# Current-LoadSwitches_1V8.net
KiCad netlist of a schematic drawn in Altium Designer
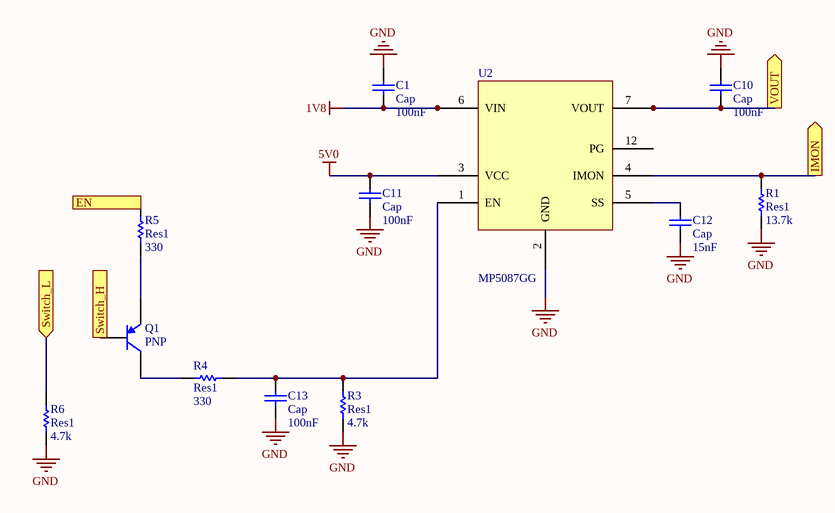
[diagram p0: Current-LoadSwitches 1V8.SchDoc]

(export (version "E")
  (design (tool "Eeschema 10.0.6"))
  (components
    (comp (ref "C1")
      (value "Cap")
      (footprint "0402-A")
      (description "Capacitor")
      (fields (field (name "ALTIUM_VALUE") "100nF") (field (name "PUBLISHER") "Altium Limited"))
      (libsource (lib "Miscellaneous Devices") (part "Cap"))
    )
    (comp (ref "C10")
      (value "Cap")
      (footprint "0402-A")
      (description "Capacitor")
      (fields (field (name "ALTIUM_VALUE") "100nF") (field (name "PUBLISHER") "Altium Limited"))
      (libsource (lib "Miscellaneous Devices") (part "Cap"))
    )
    (comp (ref "C11")
      (value "Cap")
      (footprint "0402-A")
      (description "Capacitor")
      (fields (field (name "ALTIUM_VALUE") "100nF") (field (name "PUBLISHER") "Altium Limited"))
      (libsource (lib "Miscellaneous Devices") (part "Cap"))
    )
    (comp (ref "C12")
      (value "Cap")
      (footprint "0402-A")
      (description "Capacitor")
      (fields (field (name "ALTIUM_VALUE") "15nF") (field (name "PUBLISHER") "Altium Limited"))
      (libsource (lib "Miscellaneous Devices") (part "Cap"))
    )
    (comp (ref "C13")
      (value "Cap")
      (footprint "0402-A")
      (description "Capacitor")
      (fields (field (name "ALTIUM_VALUE") "100nF") (field (name "PUBLISHER") "Altium Limited"))
      (libsource (lib "Miscellaneous Devices") (part "Cap"))
    )
    (comp (ref "Q1")
      (value "PNP")
      (footprint "SOT-23B_N")
      (description "PNP Bipolar Transistor")
      (fields (field (name "PUBLISHER") "Altium Limited"))
      (libsource (lib "Miscellaneous Devices") (part "PNP"))
    )
    (comp (ref "R1")
      (value "Res1")
      (footprint "0402-A")
      (description "Resistor")
      (fields (field (name "ALTIUM_VALUE") "13.7k") (field (name "PUBLISHER") "Altium Limited"))
      (libsource (lib "Miscellaneous Devices") (part "Res1"))
    )
    (comp (ref "R3")
      (value "Res1")
      (footprint "0402-A")
      (description "Resistor")
      (fields (field (name "ALTIUM_VALUE") "4.7k") (field (name "PUBLISHER") "Altium Limited"))
      (libsource (lib "Miscellaneous Devices") (part "Res1"))
    )
    (comp (ref "R4")
      (value "Res1")
      (footprint "0402-A")
      (description "Resistor")
      (fields (field (name "ALTIUM_VALUE") "330") (field (name "PUBLISHER") "Altium Limited"))
      (libsource (lib "Miscellaneous Devices") (part "Res1"))
    )
    (comp (ref "R5")
      (value "Res1")
      (footprint "0402-A")
      (description "Resistor")
      (fields (field (name "ALTIUM_VALUE") "330") (field (name "PUBLISHER") "Altium Limited"))
      (libsource (lib "Miscellaneous Devices") (part "Res1"))
    )
    (comp (ref "R6")
      (value "Res1")
      (footprint "0402-A")
      (description "Resistor")
      (fields (field (name "ALTIUM_VALUE") "4.7k") (field (name "PUBLISHER") "Altium Limited"))
      (libsource (lib "Miscellaneous Devices") (part "Res1"))
    )
    (comp (ref "U2")
      (value "MP5087GG")
      (footprint "MP5087GG-Z")
      (libsource (lib "MP5087GG-Z") (part "Component_1"))
    )
  )
  (nets
    (net (code "1") (name "/EN") (class "Default")
      (node (ref "R5") (pin "2") (pinfunction "2_2") (pintype "passive"))
    )
    (net (code "2") (name "/IMON") (class "Default")
      (node (ref "R1") (pin "2") (pinfunction "2_2") (pintype "passive"))
      (node (ref "U2") (pin "4") (pinfunction "IMON_4") (pintype "passive"))
    )
    (net (code "3") (name "/Switch_H") (class "Default")
      (node (ref "Q1") (pin "2") (pinfunction "B_2") (pintype "passive"))
    )
    (net (code "4") (name "/Switch_L") (class "Default")
      (node (ref "R6") (pin "2") (pinfunction "2_2") (pintype "passive"))
    )
    (net (code "5") (name "/VOUT") (class "Default")
      (node (ref "C10") (pin "1") (pinfunction "1_1") (pintype "passive"))
      (node (ref "U2") (pin "10") (pinfunction "VOUT_10") (pintype "passive"))
      (node (ref "U2") (pin "7") (pinfunction "VOUT_7") (pintype "passive"))
      (node (ref "U2") (pin "8") (pinfunction "VOUT_8") (pintype "passive"))
      (node (ref "U2") (pin "9") (pinfunction "VOUT_9") (pintype "passive"))
    )
    (net (code "6") (name "1V8") (class "Default")
      (node (ref "C1") (pin "1") (pinfunction "1_1") (pintype "passive"))
      (node (ref "U2") (pin "11") (pinfunction "VOUT_11") (pintype "passive"))
      (node (ref "U2") (pin "6") (pinfunction "VIN_6") (pintype "passive"))
    )
    (net (code "7") (name "5V0") (class "Default")
      (node (ref "C11") (pin "2") (pinfunction "2_2") (pintype "passive"))
      (node (ref "U2") (pin "3") (pinfunction "VCC_3") (pintype "passive"))
    )
    (net (code "8") (name "GND") (class "Default")
      (node (ref "C1") (pin "2") (pinfunction "2_2") (pintype "passive"))
      (node (ref "C10") (pin "2") (pinfunction "2_2") (pintype "passive"))
      (node (ref "C11") (pin "1") (pinfunction "1_1") (pintype "passive"))
      (node (ref "C12") (pin "1") (pinfunction "1_1") (pintype "passive"))
      (node (ref "C13") (pin "1") (pinfunction "1_1") (pintype "passive"))
      (node (ref "R1") (pin "1") (pinfunction "1_1") (pintype "passive"))
      (node (ref "R3") (pin "1") (pinfunction "1_1") (pintype "passive"))
      (node (ref "R6") (pin "1") (pinfunction "1_1") (pintype "passive"))
      (node (ref "U2") (pin "2") (pinfunction "GND_2") (pintype "passive"))
    )
    (net (code "9") (name "Net-(Q1-C)") (class "Default")
      (node (ref "Q1") (pin "1") (pinfunction "C_1") (pintype "passive"))
      (node (ref "R4") (pin "1") (pinfunction "1_1") (pintype "passive"))
    )
    (net (code "10") (name "Net-(Q1-E)") (class "Default")
      (node (ref "Q1") (pin "3") (pinfunction "E_3") (pintype "passive"))
      (node (ref "R5") (pin "1") (pinfunction "1_1") (pintype "passive"))
    )
    (net (code "11") (name "Net-(U2-EN)") (class "Default")
      (node (ref "C13") (pin "2") (pinfunction "2_2") (pintype "passive"))
      (node (ref "R3") (pin "2") (pinfunction "2_2") (pintype "passive"))
      (node (ref "R4") (pin "2") (pinfunction "2_2") (pintype "passive"))
      (node (ref "U2") (pin "1") (pinfunction "EN_1") (pintype "passive"))
    )
    (net (code "12") (name "Net-(U2-SS)") (class "Default")
      (node (ref "C12") (pin "2") (pinfunction "2_2") (pintype "passive"))
      (node (ref "U2") (pin "5") (pinfunction "SS_5") (pintype "passive"))
    )
    (net (code "13") (name "unconnected-(U2-PG-Pad12)") (class "Default")
      (node (ref "U2") (pin "12") (pinfunction "PG_12") (pintype "passive"))
    )
  )
)
